# Power_Supply.net
KiCad netlist of a schematic drawn in Altium Designer
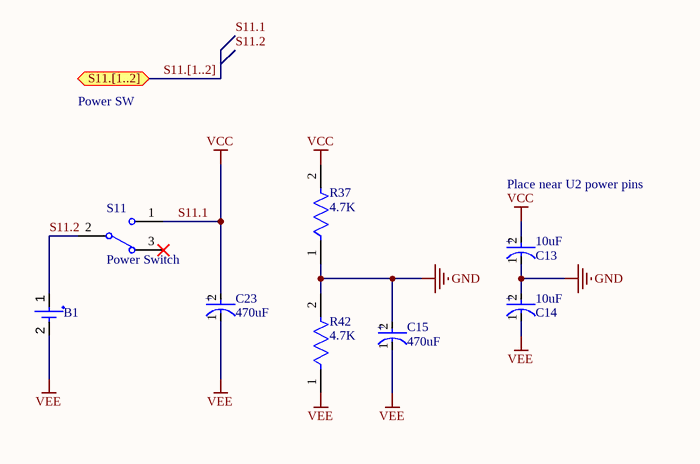
[diagram p0: Power Supply.SchDoc]

(export (version "E")
  (design (tool "Eeschema 10.0.6"))
  (components
    (comp (ref "B1")
      (value "~")
      (footprint "HDR1X2")
      (description "Hldr, Battery, PP3 (6R61), Phospher Bronze, Tin, Panel Mount, 1, Solder Lug")
      (fields (field (name "MANUFACTURER") "Bulgin") (field (name "MANUFACTURER PART NUMBER") "BX0023"))
      (libsource (lib "Miscellaneous Devices") (part "CMP-00622-2"))
    )
    (comp (ref "C13")
      (value "865080440002")
      (footprint "FP-OS-CON-SMT-A5-MFG")
      (description "CAP ALUM POLY 10UF 20% 10V SMD")
      (fields
        (field (name "MANUFACTURER") "Wurth Electronics")
        (field (name "TOLERANCE") "20%")
        (field (name "CAPACITANCE") "10uF")
      )
      (libsource (lib "Altium Content Vault") (part "a00bbbee19879c290e62620ae7e47b1"))
    )
    (comp (ref "C14")
      (value "865080440002")
      (footprint "FP-OS-CON-SMT-A5-MFG")
      (description "CAP ALUM POLY 10UF 20% 10V SMD")
      (fields
        (field (name "MANUFACTURER") "Wurth Electronics")
        (field (name "TOLERANCE") "20%")
        (field (name "CAPACITANCE") "10uF")
      )
      (libsource (lib "Altium Content Vault") (part "a00bbbee19879c290e62620ae7e47b1"))
    )
    (comp (ref "C15")
      (value "~")
      (footprint "FP-FTF-MFG")
      (fields
        (field (name "MANUFACTURER") "Wurth Electronics")
        (field (name "MANUFACTURER PART NUMBER") "865080353015")
        (field (name "TOLERANCE") "20%")
        (field (name "CAPACITANCE") "470uF")
      )
      (libsource (lib "Altium Content Vault") (part "a00bbbee19879c290e62620ae7e47b1"))
    )
    (comp (ref "C23")
      (value "~")
      (footprint "FP-FTF-MFG")
      (fields
        (field (name "MANUFACTURER") "Wurth Electronics")
        (field (name "MANUFACTURER PART NUMBER") "865080353015")
        (field (name "TOLERANCE") "20%")
        (field (name "CAPACITANCE") "470uF")
      )
      (libsource (lib "Altium Content Vault") (part "a00bbbee19879c290e62620ae7e47b1"))
    )
    (comp (ref "R37")
      (value "ESR03EZPJ472")
      (footprint "FP-ESR03-IPC_B")
      (description "4.7kΩ ±5% 0.25W 0603 Anti-Surge Chip Resistor AEC-Q200")
      (fields (field (name "TOLERANCE") "5%") (field (name "RESISTANCE") "4.7K"))
      (libsource (lib "Altium Content Vault") (part "1029c3af85768c4190bb7ad29bc67b5"))
    )
    (comp (ref "R42")
      (value "ESR03EZPJ472")
      (footprint "FP-ESR03-IPC_B")
      (description "4.7kΩ ±5% 0.25W 0603 Anti-Surge Chip Resistor AEC-Q200")
      (fields (field (name "TOLERANCE") "5%") (field (name "RESISTANCE") "4.7K"))
      (libsource (lib "Altium Content Vault") (part "1029c3af85768c4190bb7ad29bc67b5"))
    )
    (comp (ref "S11")
      (value "Power Switch")
      (footprint "HDR1X3")
      (description "Switch Toggle ON None ON SPDT Round Lever Solder Lug 5A 250VAC 28VDC Panel Mount with Threads")
      (fields
        (field (name "MANUFACTURER") "E-Switch")
        (field (name "MANUFACTURER PART NUMBER") "100SP1T1B1M1QEH")
      )
      (libsource (lib "Miscellaneous Devices") (part "SW-SPDT"))
    )
  )
  (nets
    (net (code "1") (name "/S11.2") (class "Default")
      (node (ref "B1") (pin "1") (pinfunction "+_1") (pintype "passive"))
      (node (ref "S11") (pin "2") (pinfunction "2_2") (pintype "passive"))
    )
    (net (code "3") (name "GND") (class "Default")
      (node (ref "C13") (pin "1") (pinfunction "C_1") (pintype "passive"))
      (node (ref "C14") (pin "2") (pinfunction "A_2") (pintype "passive"))
      (node (ref "C15") (pin "2") (pinfunction "A_2") (pintype "passive"))
      (node (ref "R37") (pin "1") (pinfunction "1_1") (pintype "passive"))
      (node (ref "R42") (pin "2") (pinfunction "2_2") (pintype "passive"))
    )
    (net (code "4") (name "VCC") (class "Default")
      (node (ref "C13") (pin "2") (pinfunction "A_2") (pintype "passive"))
      (node (ref "C23") (pin "2") (pinfunction "A_2") (pintype "passive"))
      (node (ref "R37") (pin "2") (pinfunction "2_2") (pintype "passive"))
      (node (ref "S11") (pin "1") (pinfunction "1_1") (pintype "passive"))
    )
    (net (code "5") (name "VEE") (class "Default")
      (node (ref "B1") (pin "2") (pinfunction "-_2") (pintype "passive"))
      (node (ref "C14") (pin "1") (pinfunction "C_1") (pintype "passive"))
      (node (ref "C15") (pin "1") (pinfunction "C_1") (pintype "passive"))
      (node (ref "C23") (pin "1") (pinfunction "C_1") (pintype "passive"))
      (node (ref "R42") (pin "1") (pinfunction "1_1") (pintype "passive"))
    )
    (net (code "6") (name "unconnected-(S11-Pad3)") (class "Default")
      (node (ref "S11") (pin "3") (pinfunction "3_3") (pintype "passive+no_connect"))
    )
  )
)
